# GPS.net
KiCad netlist of a schematic drawn in EAGLE
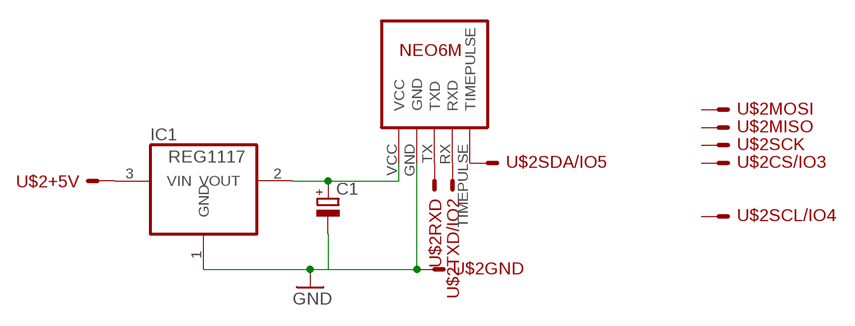
[diagram p0: schematic, sheet 1]

(export (version "E")
  (design (tool "Eeschema 10.0.6"))
  (components
    (comp (ref "C1")
      (value "CPOL-EUB45181A")
      (footprint "eagle-import:B45181A")
      (libsource (lib "eagle-import") (part "CPOL-EUB45181A"))
    )
    (comp (ref "IC1")
      (value "REG1117")
      (footprint "eagle-import:SOT223")
      (libsource (lib "eagle-import") (part "REG1117"))
    )
    (comp (ref "U$1")
      (value "NEO6M")
      (footprint "eagle-import:NEO6M")
      (libsource (lib "eagle-import") (part "NEO6M"))
    )
    (comp (ref "U$2")
      (value "LIMERO_BUS")
      (footprint "eagle-import:SPI_BUS")
      (libsource (lib "eagle-import") (part "LIMERO_BUS"))
    )
  )
  (nets
    (net (code "1") (name "GND") (class "Default")
      (node (ref "C1") (pin "-") (pinfunction "-_-") (pintype "passive"))
      (node (ref "IC1") (pin "1") (pinfunction "GND_1") (pintype "power_in"))
      (node (ref "U$1") (pin "GND") (pinfunction "GND_GND") (pintype "power_in"))
      (node (ref "U$2") (pin "GND") (pinfunction "S_GND") (pintype "passive"))
    )
    (net (code "2") (name "Net-(IC1-VIN)") (class "Default")
      (node (ref "IC1") (pin "3") (pinfunction "VIN_3") (pintype "input"))
      (node (ref "U$2") (pin "+5V") (pinfunction "S_+5V") (pintype "passive"))
    )
    (net (code "3") (name "Net-(IC1-VOUT)") (class "Default")
      (node (ref "C1") (pin "+") (pinfunction "+_+") (pintype "passive"))
      (node (ref "IC1") (pin "2") (pinfunction "VOUT_2") (pintype "output"))
      (node (ref "U$1") (pin "VCC") (pinfunction "VCC_VCC") (pintype "power_in"))
    )
    (net (code "4") (name "Net-(U$1-RXD)") (class "Default")
      (node (ref "U$1") (pin "RX") (pinfunction "RXD_RX") (pintype "bidirectional"))
      (node (ref "U$2") (pin "TXD") (pinfunction "S_TXD") (pintype "passive"))
    )
    (net (code "5") (name "Net-(U$1-TXD)") (class "Default")
      (node (ref "U$1") (pin "TX") (pinfunction "TXD_TX") (pintype "bidirectional"))
      (node (ref "U$2") (pin "RXD") (pinfunction "S_RXD") (pintype "passive"))
    )
    (net (code "6") (name "Net-(U$2I-S)") (class "Default")
      (node (ref "U$1") (pin "TIMEPULSE") (pinfunction "TIMEPULSE_TIMEPULSE") (pintype "bidirectional"))
      (node (ref "U$2") (pin "SDA") (pinfunction "S_SDA") (pintype "passive"))
    )
    (net (code "7") (name "unconnected-(U$2B-S-PadCS)") (class "Default")
      (node (ref "U$2") (pin "CS") (pinfunction "S_CS") (pintype "passive"))
    )
    (net (code "8") (name "unconnected-(U$2D-S-PadMISO)") (class "Default")
      (node (ref "U$2") (pin "MISO") (pinfunction "S_MISO") (pintype "passive"))
    )
    (net (code "9") (name "unconnected-(U$2E-S-PadMOSI)") (class "Default")
      (node (ref "U$2") (pin "MOSI") (pinfunction "S_MOSI") (pintype "passive"))
    )
    (net (code "10") (name "unconnected-(U$2G-S-PadSCK)") (class "Default")
      (node (ref "U$2") (pin "SCK") (pinfunction "S_SCK") (pintype "passive"))
    )
    (net (code "11") (name "unconnected-(U$2H-S-PadSCL)") (class "Default")
      (node (ref "U$2") (pin "SCL") (pinfunction "S_SCL") (pintype "passive"))
    )
  )
)
